# LTC4365-Evaluation.net
KiCad netlist of a schematic drawn in EAGLE
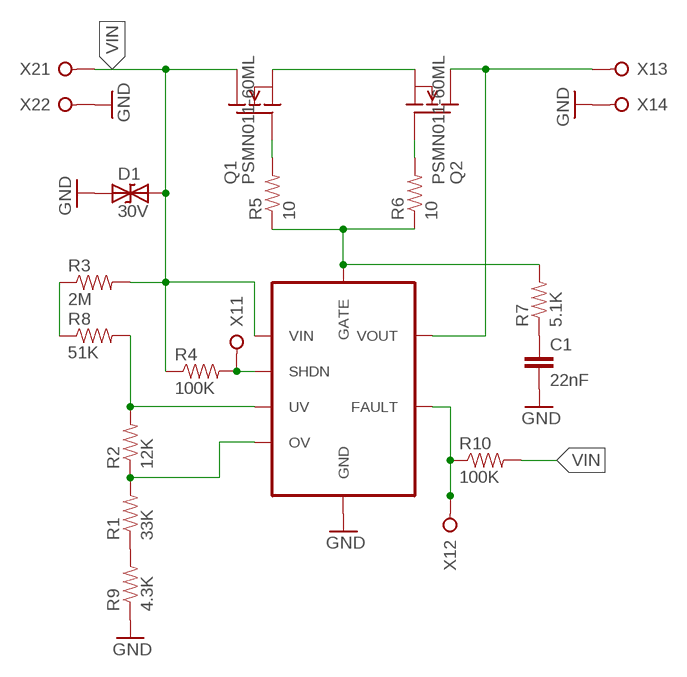
[diagram p0: schematic, sheet 1]

(export (version "E")
  (design (tool "Eeschema 10.0.6"))
  (components
    (comp (ref "C1")
      (value "22nF")
      (footprint "eagle-import:CAPACITOR-0805")
      (libsource (lib "eagle-import") (part "CAPACITOR-0805"))
    )
    (comp (ref "D1")
      (value "30V")
      (footprint "eagle-import:TVS-DO-201")
      (libsource (lib "eagle-import") (part "TVS-DO-201"))
    )
    (comp (ref "IC1")
      (value "LTC4365")
      (footprint "eagle-import:SOT-23-8")
      (libsource (lib "eagle-import") (part "LTC4365"))
    )
    (comp (ref "Q1")
      (value "PSMN011-60ML")
      (footprint "eagle-import:LFPAK33")
      (libsource (lib "eagle-import") (part "PSMN011-60ML"))
    )
    (comp (ref "Q2")
      (value "PSMN011-60ML")
      (footprint "eagle-import:LFPAK33")
      (libsource (lib "eagle-import") (part "PSMN011-60ML"))
    )
    (comp (ref "R1")
      (value "33K")
      (footprint "eagle-import:RESISTOR-0805")
      (libsource (lib "eagle-import") (part "RESISTOR-0805"))
    )
    (comp (ref "R2")
      (value "12K")
      (footprint "eagle-import:RESISTOR-0805")
      (libsource (lib "eagle-import") (part "RESISTOR-0805"))
    )
    (comp (ref "R3")
      (value "2M")
      (footprint "eagle-import:RESISTOR-0805")
      (libsource (lib "eagle-import") (part "RESISTOR-0805"))
    )
    (comp (ref "R4")
      (value "100K")
      (footprint "eagle-import:RESISTOR-0805")
      (libsource (lib "eagle-import") (part "RESISTOR-0805"))
    )
    (comp (ref "R5")
      (value "10")
      (footprint "eagle-import:AXIAL-7.5MM")
      (libsource (lib "eagle-import") (part "RESISTOR-7.5MM"))
    )
    (comp (ref "R6")
      (value "10")
      (footprint "eagle-import:RESISTOR-0805")
      (libsource (lib "eagle-import") (part "RESISTOR-0805"))
    )
    (comp (ref "R7")
      (value "5.1K")
      (footprint "eagle-import:RESISTOR-0805")
      (libsource (lib "eagle-import") (part "RESISTOR-0805"))
    )
    (comp (ref "R8")
      (value "51K")
      (footprint "eagle-import:RESISTOR-0805")
      (libsource (lib "eagle-import") (part "RESISTOR-0805"))
    )
    (comp (ref "R9")
      (value "4.3K")
      (footprint "eagle-import:RESISTOR-0805")
      (libsource (lib "eagle-import") (part "RESISTOR-0805"))
    )
    (comp (ref "R10")
      (value "100K")
      (footprint "eagle-import:RESISTOR-0805")
      (libsource (lib "eagle-import") (part "RESISTOR-0805"))
    )
    (comp (ref "X1")
      (value "SCREW-TERM-4")
      (footprint "eagle-import:SCREW-TERM-4")
      (libsource (lib "eagle-import") (part "SCREW-TERM-4"))
    )
    (comp (ref "X2")
      (value "SCREW-TERM-2")
      (footprint "eagle-import:SCREW-TERM-2")
      (libsource (lib "eagle-import") (part "SCREW-TERM-2"))
    )
  )
  (nets
    (net (code "1") (name "GND") (class "Default")
      (node (ref "C1") (pin "2") (pinfunction "2_2") (pintype "passive"))
      (node (ref "D1") (pin "1") (pinfunction "1_1") (pintype "passive"))
      (node (ref "IC1") (pin "4") (pinfunction "GND_4") (pintype "passive"))
      (node (ref "R9") (pin "1") (pinfunction "1_1") (pintype "passive"))
      (node (ref "X1") (pin "4") (pinfunction "KL_4") (pintype "passive"))
      (node (ref "X2") (pin "2") (pinfunction "KL_2") (pintype "passive"))
    )
    (net (code "2") (name "Net-(C1-Pad1)") (class "Default")
      (node (ref "C1") (pin "1") (pinfunction "1_1") (pintype "passive"))
      (node (ref "R7") (pin "1") (pinfunction "1_1") (pintype "passive"))
    )
    (net (code "3") (name "Net-(IC1-FAULT)") (class "Default")
      (node (ref "IC1") (pin "6") (pinfunction "FAULT_6") (pintype "output"))
      (node (ref "R10") (pin "1") (pinfunction "1_1") (pintype "passive"))
      (node (ref "X1") (pin "2") (pinfunction "KL_2") (pintype "passive"))
    )
    (net (code "4") (name "Net-(IC1-GATE)") (class "Default")
      (node (ref "IC1") (pin "8") (pinfunction "GATE_8") (pintype "output"))
      (node (ref "R5") (pin "P$1") (pinfunction "1_P$1") (pintype "passive"))
      (node (ref "R6") (pin "1") (pinfunction "1_1") (pintype "passive"))
      (node (ref "R7") (pin "2") (pinfunction "2_2") (pintype "passive"))
    )
    (net (code "5") (name "Net-(IC1-OV)") (class "Default")
      (node (ref "IC1") (pin "3") (pinfunction "OV_3") (pintype "input"))
      (node (ref "R1") (pin "2") (pinfunction "2_2") (pintype "passive"))
      (node (ref "R2") (pin "1") (pinfunction "1_1") (pintype "passive"))
    )
    (net (code "6") (name "Net-(IC1-SHDN)") (class "Default")
      (node (ref "IC1") (pin "5") (pinfunction "SHDN_5") (pintype "input"))
      (node (ref "R4") (pin "2") (pinfunction "2_2") (pintype "passive"))
      (node (ref "X1") (pin "1") (pinfunction "KL_1") (pintype "passive"))
    )
    (net (code "7") (name "Net-(IC1-UV)") (class "Default")
      (node (ref "IC1") (pin "2") (pinfunction "UV_2") (pintype "input"))
      (node (ref "R2") (pin "2") (pinfunction "2_2") (pintype "passive"))
      (node (ref "R8") (pin "2") (pinfunction "2_2") (pintype "passive"))
    )
    (net (code "8") (name "Net-(IC1-VOUT)") (class "Default")
      (node (ref "IC1") (pin "7") (pinfunction "VOUT_7") (pintype "input"))
      (node (ref "Q2") (pin "MB") (pinfunction "DRN_MB") (pintype "passive"))
      (node (ref "X1") (pin "3") (pinfunction "KL_3") (pintype "passive"))
    )
    (net (code "9") (name "Net-(Q1-GATE)") (class "Default")
      (node (ref "Q1") (pin "4") (pinfunction "GATE_4") (pintype "passive"))
      (node (ref "R5") (pin "P$2") (pinfunction "2_P$2") (pintype "passive"))
    )
    (net (code "10") (name "Net-(Q1-SRC-Pad1)") (class "Default")
      (node (ref "Q1") (pin "1") (pinfunction "SRC_1") (pintype "passive"))
      (node (ref "Q1") (pin "2") (pinfunction "SRC_2") (pintype "passive"))
      (node (ref "Q1") (pin "3") (pinfunction "SRC_3") (pintype "passive"))
      (node (ref "Q2") (pin "1") (pinfunction "SRC_1") (pintype "passive"))
      (node (ref "Q2") (pin "2") (pinfunction "SRC_2") (pintype "passive"))
      (node (ref "Q2") (pin "3") (pinfunction "SRC_3") (pintype "passive"))
    )
    (net (code "11") (name "Net-(Q2-GATE)") (class "Default")
      (node (ref "Q2") (pin "4") (pinfunction "GATE_4") (pintype "passive"))
      (node (ref "R6") (pin "2") (pinfunction "2_2") (pintype "passive"))
    )
    (net (code "12") (name "Net-(R1-Pad1)") (class "Default")
      (node (ref "R1") (pin "1") (pinfunction "1_1") (pintype "passive"))
      (node (ref "R9") (pin "2") (pinfunction "2_2") (pintype "passive"))
    )
    (net (code "13") (name "Net-(R3-Pad1)") (class "Default")
      (node (ref "R3") (pin "1") (pinfunction "1_1") (pintype "passive"))
      (node (ref "R8") (pin "1") (pinfunction "1_1") (pintype "passive"))
    )
    (net (code "14") (name "VIN") (class "Default")
      (node (ref "D1") (pin "2") (pinfunction "2_2") (pintype "passive"))
      (node (ref "IC1") (pin "1") (pinfunction "VIN_1") (pintype "power_in"))
      (node (ref "Q1") (pin "MB") (pinfunction "DRN_MB") (pintype "passive"))
      (node (ref "R10") (pin "2") (pinfunction "2_2") (pintype "passive"))
      (node (ref "R3") (pin "2") (pinfunction "2_2") (pintype "passive"))
      (node (ref "R4") (pin "1") (pinfunction "1_1") (pintype "passive"))
      (node (ref "X2") (pin "1") (pinfunction "KL_1") (pintype "passive"))
    )
  )
)
